# PreampTX.net
KiCad netlist of a schematic drawn in Altium Designer
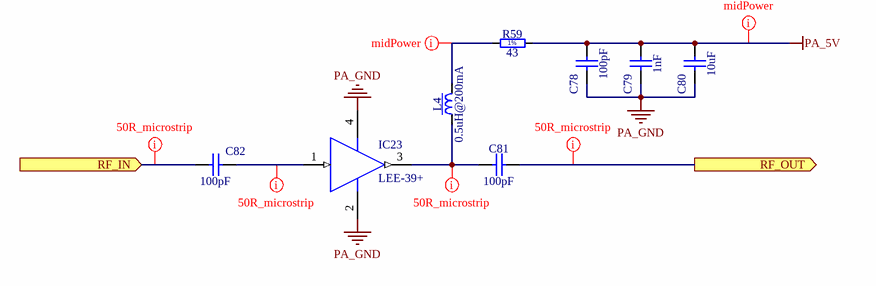
[diagram p0: PreampTX.SchDoc]

(export (version "E")
  (design (tool "Eeschema 10.0.6"))
  (components
    (comp (ref "C78")
      (value "100pF")
      (footprint "CAPC1005X55N")
      (description "Non-polarised capacitor")
      (fields
        (field (name "PART NUMBER") "CC0402_100PF_50V_5%_C0G")
        (field (name "VOLTAGE") "50V")
        (field (name "AUTHOR") "CERN DEM JLC")
      )
      (libsource (lib "Capacitors") (part "Capacitor - non polarized"))
    )
    (comp (ref "C79")
      (value "1nF")
      (footprint "CAPC1005X55N")
      (description "Non-polarised capacitor")
      (fields
        (field (name "PART NUMBER") "CC0402_1NF_50V_10%_X7R")
        (field (name "VOLTAGE") "50V")
        (field (name "AUTHOR") "CERN DEM JLC")
      )
      (libsource (lib "Capacitors") (part "Capacitor - non polarized"))
    )
    (comp (ref "C80")
      (value "10uF")
      (footprint "CAPC3216X180N")
      (description "Non-polarised capacitor")
      (fields
        (field (name "PART NUMBER") "CC1206_10UF_25V_10%_X7R")
        (field (name "VOLTAGE") "25V")
        (field (name "AUTHOR") "CERN DEM JLC")
      )
      (libsource (lib "Capacitors") (part "Capacitor - non polarized"))
    )
    (comp (ref "C81")
      (value "100pF")
      (footprint "CAPC1005X55N")
      (description "Non-polarised capacitor")
      (fields
        (field (name "PART NUMBER") "CC0402_100PF_50V_5%_C0G")
        (field (name "VOLTAGE") "50V")
        (field (name "AUTHOR") "CERN DEM JLC")
      )
      (libsource (lib "Capacitors") (part "Capacitor - non polarized"))
    )
    (comp (ref "C82")
      (value "100pF")
      (footprint "CAPC1005X55N")
      (description "Non-polarised capacitor")
      (fields
        (field (name "PART NUMBER") "CC0402_100PF_50V_5%_C0G")
        (field (name "VOLTAGE") "50V")
        (field (name "AUTHOR") "CERN DEM JLC")
      )
      (libsource (lib "Capacitors") (part "Capacitor - non polarized"))
    )
    (comp (ref "IC23")
      (value "LEE-39+")
      (footprint "MINI-CIRCUITS_FG873")
      (description "Monolithic Amplifier")
      (fields (field (name "MANUFACTURER") "MINI-CIRCUITS") (field (name "AUTHOR") "CERN DEM JLC"))
      (libsource (lib "ICs And Semiconductors") (part "Monolithic Amplifier Type 1"))
    )
    (comp (ref "L4")
      (value "0.5uH@200mA")
      (footprint "IND_MINI-CIRCUITS_GU1604")
      (description "50 Ohms, 50 to 8200 MHz RF Choke")
      (fields
        (field (name "PART NUMBER") "IND_MINI-CIRCUITS_TCCH-80+")
        (field (name "POWER") "200mA")
        (field (name "AUTHOR") "CERN DEM JLC")
      )
      (libsource (lib "Inductors & Transformers") (part "IND_MINI-CIRCUITS_TCCH-80+"))
    )
    (comp (ref "R59")
      (value "43")
      (footprint "RESC1608X55N")
      (description "Resistor - 1%")
      (fields
        (field (name "PART NUMBER") "R0603_43R_1%_0.1W_100PPM")
        (field (name "POWER") "0.1W")
        (field (name "AUTHOR") "CERN DEM JLC")
      )
      (libsource (lib "Resistors") (part "Resistor - 1%"))
    )
  )
  (nets
    (net (code "1") (name "/RF_IN") (class "Default")
      (node (ref "C82") (pin "1") (pinfunction "1_1") (pintype "passive"))
    )
    (net (code "2") (name "/RF_OUT") (class "Default")
      (node (ref "C81") (pin "2") (pinfunction "2_2") (pintype "passive"))
    )
    (net (code "3") (name "Net-(IC23-RF_IN)") (class "Default")
      (node (ref "C82") (pin "2") (pinfunction "2_2") (pintype "passive"))
      (node (ref "IC23") (pin "1") (pinfunction "RF_IN_1") (pintype "input"))
    )
    (net (code "4") (name "Net-(IC23-RF_OUT)") (class "Default")
      (node (ref "C81") (pin "1") (pinfunction "1_1") (pintype "passive"))
      (node (ref "IC23") (pin "3") (pinfunction "RF_OUT_3") (pintype "output"))
      (node (ref "L4") (pin "1") (pinfunction "1_1") (pintype "passive"))
    )
    (net (code "5") (name "Net-(L4-Pad3)") (class "Default")
      (node (ref "L4") (pin "3") (pinfunction "3_3") (pintype "passive"))
      (node (ref "R59") (pin "1") (pinfunction "1_1") (pintype "passive"))
    )
    (net (code "6") (name "PA_5V") (class "Default")
      (node (ref "C78") (pin "2") (pinfunction "2_2") (pintype "passive"))
      (node (ref "C79") (pin "2") (pinfunction "2_2") (pintype "passive"))
      (node (ref "C80") (pin "2") (pinfunction "2_2") (pintype "passive"))
      (node (ref "R59") (pin "2") (pinfunction "2_2") (pintype "passive"))
    )
    (net (code "7") (name "PA_GND") (class "Default")
      (node (ref "C78") (pin "1") (pinfunction "1_1") (pintype "passive"))
      (node (ref "C79") (pin "1") (pinfunction "1_1") (pintype "passive"))
      (node (ref "C80") (pin "1") (pinfunction "1_1") (pintype "passive"))
      (node (ref "IC23") (pin "2") (pinfunction "GND_2") (pintype "power_in"))
      (node (ref "IC23") (pin "4") (pinfunction "GND_4") (pintype "power_in"))
    )
  )
)
